# Arduino_Shield.net
KiCad netlist of a schematic drawn in Altium Designer
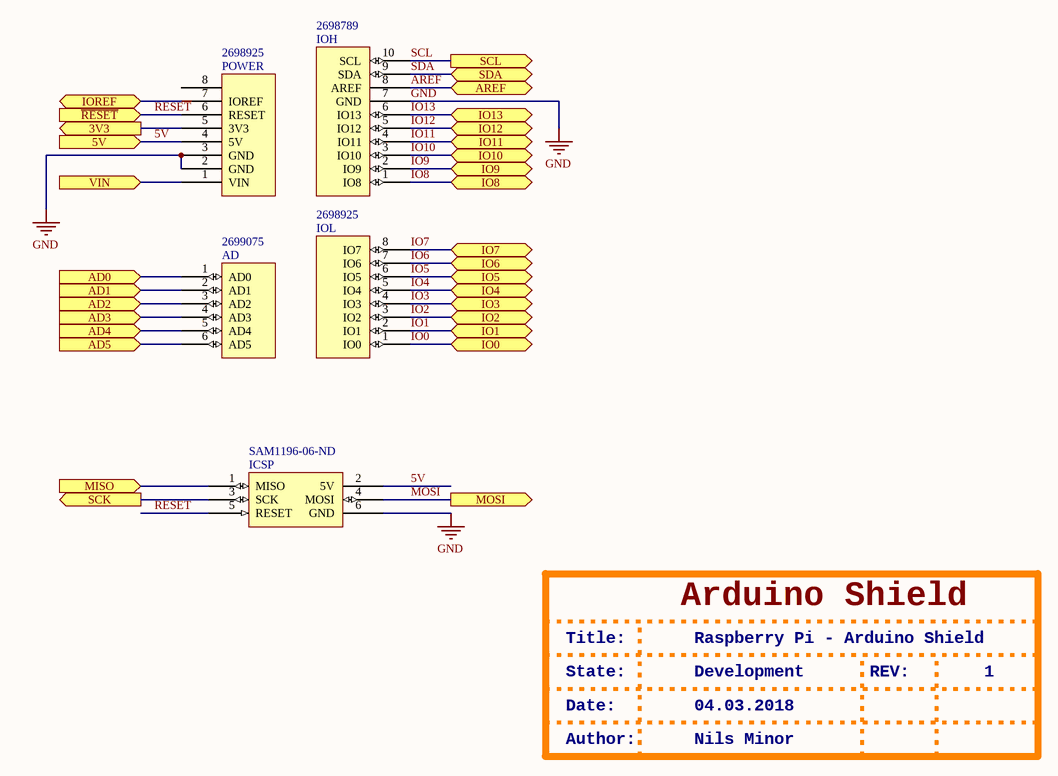
[diagram p0: Arduino Shield.SchDoc]

(export (version "E")
  (design (tool "Eeschema 10.0.6"))
  (components
    (comp (ref "AD")
      (value "AD")
      (footprint "Header 6x1 8.5mm")
      (fields (field (name "SUPPLIER PART NUMBER 4") "2699075"))
      (libsource (lib "rpi") (part "AD"))
    )
    (comp (ref "ICSP")
      (value "ICSP")
      (footprint "ICSP")
      (fields (field (name "SUPPLIER PART NUMBER 5") "SAM1196-06-ND"))
      (libsource (lib "rpi") (part "ICSP"))
    )
    (comp (ref "IOH")
      (value "IOH")
      (footprint "Header 10x1 8.5mm")
      (fields (field (name "SUPPLIER PART NUMBER 3") "2698789"))
      (libsource (lib "rpi") (part "IOH"))
    )
    (comp (ref "IOL")
      (value "IOL")
      (footprint "Header 8x1 8.5mm")
      (fields (field (name "SUPPLIER PART NUMBER 4") "2698925"))
      (libsource (lib "rpi") (part "IOL"))
    )
    (comp (ref "POWER")
      (value "POWER_UNO")
      (footprint "Header 8x1 8.5mm")
      (fields (field (name "SUPPLIER PART NUMBER 4") "2698925"))
      (libsource (lib "rpi") (part "POWER_UNO"))
    )
  )
  (nets
    (net (code "1") (name "/3V3") (class "Default")
      (node (ref "POWER") (pin "5") (pinfunction "3V3_5") (pintype "power_in"))
    )
    (net (code "2") (name "/5V") (class "Default")
      (node (ref "ICSP") (pin "2") (pinfunction "5V_2") (pintype "power_in"))
      (node (ref "POWER") (pin "4") (pinfunction "5V_4") (pintype "power_in"))
    )
    (net (code "4") (name "/AD0") (class "Default")
      (node (ref "AD") (pin "1") (pinfunction "AD0_1") (pintype "bidirectional"))
    )
    (net (code "5") (name "/AD1") (class "Default")
      (node (ref "AD") (pin "2") (pinfunction "AD1_2") (pintype "bidirectional"))
    )
    (net (code "6") (name "/AD2") (class "Default")
      (node (ref "AD") (pin "3") (pinfunction "AD2_3") (pintype "bidirectional"))
    )
    (net (code "7") (name "/AD3") (class "Default")
      (node (ref "AD") (pin "4") (pinfunction "AD3_4") (pintype "bidirectional"))
    )
    (net (code "8") (name "/AD4") (class "Default")
      (node (ref "AD") (pin "5") (pinfunction "AD4_5") (pintype "bidirectional"))
    )
    (net (code "9") (name "/AD5") (class "Default")
      (node (ref "AD") (pin "6") (pinfunction "AD5_6") (pintype "bidirectional"))
    )
    (net (code "10") (name "/AREF") (class "Default")
      (node (ref "IOH") (pin "8") (pinfunction "AREF_8") (pintype "passive"))
    )
    (net (code "11") (name "/IO0") (class "Default")
      (node (ref "IOL") (pin "1") (pinfunction "IO0_1") (pintype "bidirectional"))
    )
    (net (code "12") (name "/IO1") (class "Default")
      (node (ref "IOL") (pin "2") (pinfunction "IO1_2") (pintype "bidirectional"))
    )
    (net (code "13") (name "/IO2") (class "Default")
      (node (ref "IOL") (pin "3") (pinfunction "IO2_3") (pintype "bidirectional"))
    )
    (net (code "14") (name "/IO3") (class "Default")
      (node (ref "IOL") (pin "4") (pinfunction "IO3_4") (pintype "bidirectional"))
    )
    (net (code "15") (name "/IO4") (class "Default")
      (node (ref "IOL") (pin "5") (pinfunction "IO4_5") (pintype "bidirectional"))
    )
    (net (code "16") (name "/IO5") (class "Default")
      (node (ref "IOL") (pin "6") (pinfunction "IO5_6") (pintype "bidirectional"))
    )
    (net (code "17") (name "/IO6") (class "Default")
      (node (ref "IOL") (pin "7") (pinfunction "IO6_7") (pintype "bidirectional"))
    )
    (net (code "18") (name "/IO7") (class "Default")
      (node (ref "IOL") (pin "8") (pinfunction "IO7_8") (pintype "bidirectional"))
    )
    (net (code "19") (name "/IO8") (class "Default")
      (node (ref "IOH") (pin "1") (pinfunction "IO8_1") (pintype "bidirectional"))
    )
    (net (code "20") (name "/IO9") (class "Default")
      (node (ref "IOH") (pin "2") (pinfunction "IO9_2") (pintype "bidirectional"))
    )
    (net (code "21") (name "/IO10") (class "Default")
      (node (ref "IOH") (pin "3") (pinfunction "IO10_3") (pintype "bidirectional"))
    )
    (net (code "22") (name "/IO11") (class "Default")
      (node (ref "IOH") (pin "4") (pinfunction "IO11_4") (pintype "bidirectional"))
    )
    (net (code "23") (name "/IO12") (class "Default")
      (node (ref "IOH") (pin "5") (pinfunction "IO12_5") (pintype "bidirectional"))
    )
    (net (code "24") (name "/IO13") (class "Default")
      (node (ref "IOH") (pin "6") (pinfunction "IO13_6") (pintype "bidirectional"))
    )
    (net (code "25") (name "/IOREF") (class "Default")
      (node (ref "POWER") (pin "7") (pinfunction "IOREF_7") (pintype "power_in"))
    )
    (net (code "26") (name "/MISO") (class "Default")
      (node (ref "ICSP") (pin "1") (pinfunction "MISO_1") (pintype "bidirectional"))
    )
    (net (code "27") (name "/MOSI") (class "Default")
      (node (ref "ICSP") (pin "4") (pinfunction "MOSI_4") (pintype "bidirectional"))
    )
    (net (code "28") (name "/SCK") (class "Default")
      (node (ref "ICSP") (pin "3") (pinfunction "SCK_3") (pintype "bidirectional"))
    )
    (net (code "29") (name "/SCL") (class "Default")
      (node (ref "IOH") (pin "10") (pinfunction "SCL_10") (pintype "bidirectional"))
    )
    (net (code "30") (name "/SDA") (class "Default")
      (node (ref "IOH") (pin "9") (pinfunction "SDA_9") (pintype "bidirectional"))
    )
    (net (code "31") (name "/VIN") (class "Default")
      (node (ref "POWER") (pin "1") (pinfunction "VIN_1") (pintype "power_in"))
    )
    (net (code "32") (name "/~{RESET}") (class "Default")
      (node (ref "ICSP") (pin "5") (pinfunction "RESET_5") (pintype "input"))
      (node (ref "POWER") (pin "6") (pinfunction "RESET_6") (pintype "passive"))
    )
    (net (code "33") (name "GND") (class "Default")
      (node (ref "ICSP") (pin "6") (pinfunction "GND_6") (pintype "power_in"))
      (node (ref "IOH") (pin "7") (pinfunction "GND_7") (pintype "power_in"))
      (node (ref "POWER") (pin "2") (pinfunction "GND_2") (pintype "power_in"))
      (node (ref "POWER") (pin "3") (pinfunction "GND_3") (pintype "power_in"))
    )
    (net (code "34") (name "unconnected-(POWER-Pad8)") (class "Default")
      (node (ref "POWER") (pin "8") (pintype "passive"))
    )
  )
)
